# DS-1.net
KiCad netlist of a schematic drawn in Altium Designer
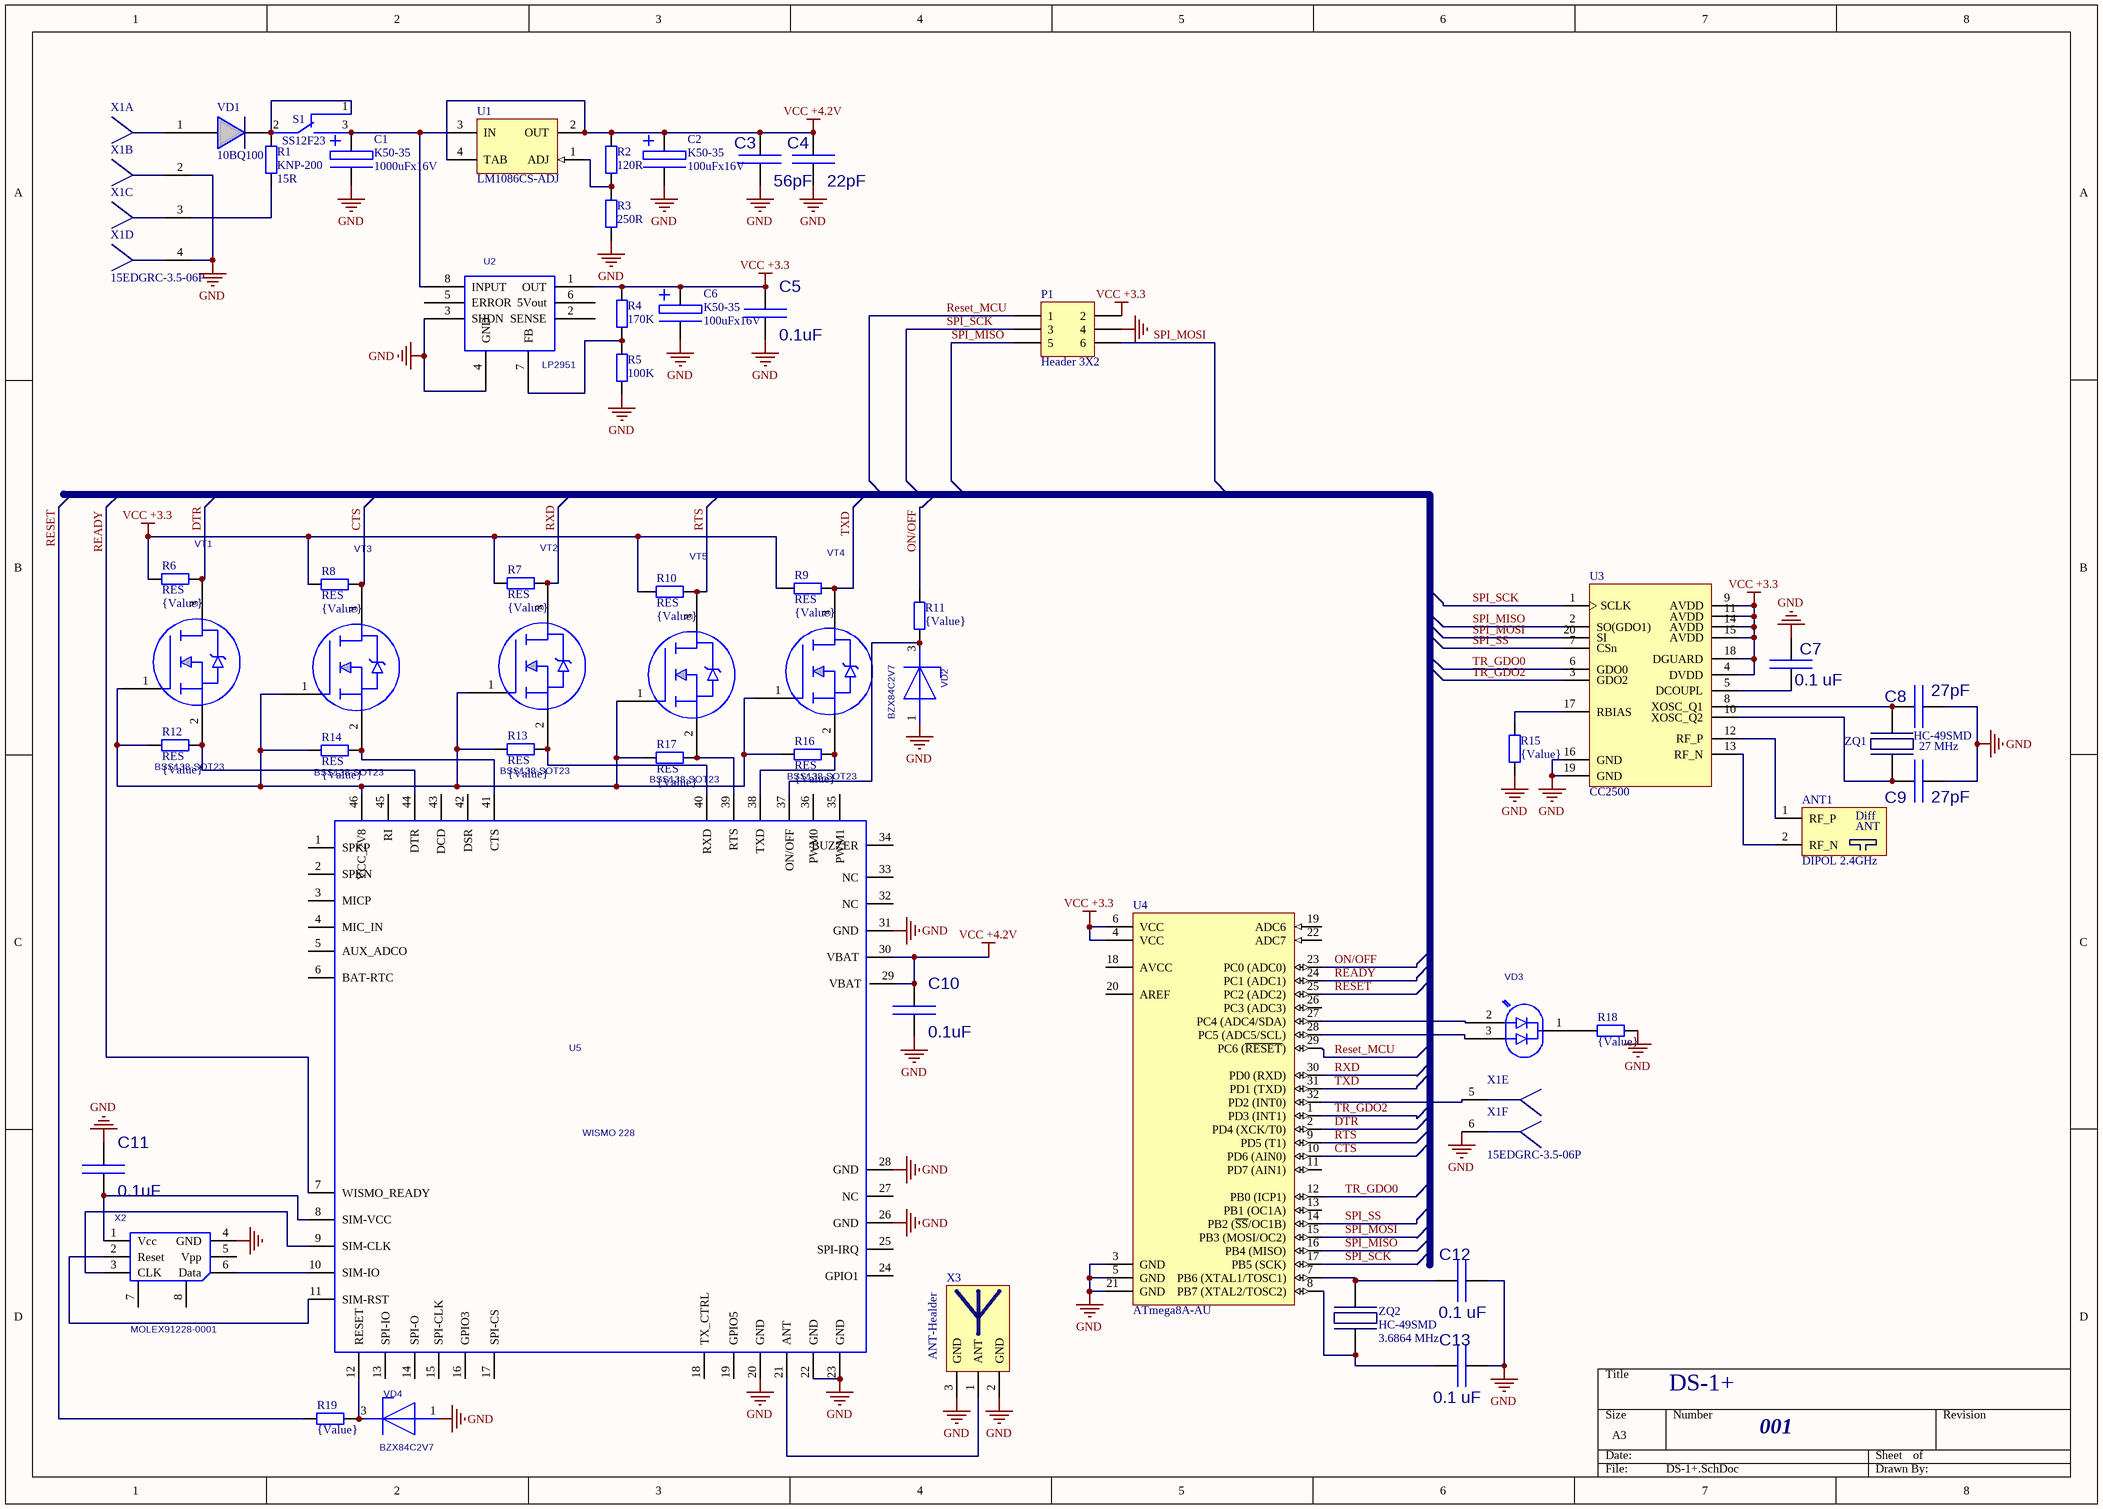
[diagram p0: DS-1+.SchDoc]

(export (version "E")
  (design (tool "Eeschema 10.0.6"))
  (components
    (comp (ref "ANT1")
      (value "DIPOL 2.4GHz")
      (footprint "ANT_Dipol_2.4GHz")
      (libsource (lib "NEW") (part "ANT_dipol_2.4GHz"))
    )
    (comp (ref "C1")
      (value "K50-35")
      (footprint "CAP_POL_D10")
      (fields (field (name "ALTIUM_VALUE") "1000uFx16V"))
      (libsource (lib "NEW") (part "Capasitor_pol D10"))
    )
    (comp (ref "C2")
      (value "K50-35")
      (footprint "CAP_POL_D6.3")
      (fields (field (name "ALTIUM_VALUE") "100uFx16V"))
      (libsource (lib "NEW") (part "Capasitor_pol D6.3"))
    )
    (comp (ref "C3")
      (value "56pF")
      (footprint "C0805")
      (description "KONDENS_SMD")
      (libsource (lib "NEW") (part "KONDENS_SMD"))
    )
    (comp (ref "C4")
      (value "22pF")
      (footprint "C0805")
      (description "KONDENS_SMD")
      (libsource (lib "NEW") (part "KONDENS_SMD"))
    )
    (comp (ref "C5")
      (value "0.1uF")
      (footprint "C0805")
      (description "KONDENS_SMD")
      (libsource (lib "NEW") (part "KONDENS_SMD"))
    )
    (comp (ref "C6")
      (value "K50-35")
      (footprint "CAP_POL_D6.3")
      (fields (field (name "ALTIUM_VALUE") "100uFx16V"))
      (libsource (lib "NEW") (part "Capasitor_pol D6.3"))
    )
    (comp (ref "C7")
      (value "0.1 uF")
      (footprint "C0805")
      (description "KONDENS_SMD")
      (libsource (lib "NEW") (part "KONDENS_SMD"))
    )
    (comp (ref "C8")
      (value "27pF")
      (footprint "C0805")
      (description "KONDENS_SMD")
      (libsource (lib "NEW") (part "KONDENS_SMD"))
    )
    (comp (ref "C9")
      (value "27pF")
      (footprint "C0805")
      (description "KONDENS_SMD")
      (libsource (lib "NEW") (part "KONDENS_SMD"))
    )
    (comp (ref "C10")
      (value "0.1uF")
      (footprint "C0805")
      (description "KONDENS_SMD")
      (libsource (lib "NEW") (part "KONDENS_SMD"))
    )
    (comp (ref "C11")
      (value "0.1uF")
      (footprint "C0805")
      (description "KONDENS_SMD")
      (libsource (lib "NEW") (part "KONDENS_SMD"))
    )
    (comp (ref "C12")
      (value "0.1 uF")
      (footprint "C0805")
      (description "KONDENS_SMD")
      (libsource (lib "NEW") (part "KONDENS_SMD"))
    )
    (comp (ref "C13")
      (value "0.1 uF")
      (footprint "C0805")
      (description "KONDENS_SMD")
      (libsource (lib "NEW") (part "KONDENS_SMD"))
    )
    (comp (ref "P1")
      (value "Header 3X2")
      (footprint "HDR2X3")
      (description "Header, 3-Pin, Dual row")
      (fields (field (name "PUBLISHER") "Altium Limited"))
      (libsource (lib "Miscellaneous Connectors") (part "Header 3X2"))
    )
    (comp (ref "R1")
      (value "KNP-200")
      (footprint "Resistor KNP-200")
      (fields (field (name "ALTIUM_VALUE") "15R"))
      (libsource (lib "NEW") (part "Resistor 2W"))
    )
    (comp (ref "R2")
      (value "120R")
      (footprint "C0805")
      (description "Resistor")
      (fields (field (name "Comment") "RES"))
      (libsource (lib "") (part "RES_1"))
    )
    (comp (ref "R3")
      (value "250R")
      (footprint "C0805")
      (description "Resistor")
      (fields (field (name "Comment") "RES"))
      (libsource (lib "") (part "RES_1"))
    )
    (comp (ref "R4")
      (value "170K")
      (footprint "C0805")
      (description "Resistor")
      (fields (field (name "Comment") "RES"))
      (libsource (lib "") (part "RES_1"))
    )
    (comp (ref "R5")
      (value "100K")
      (footprint "C0805")
      (description "Resistor")
      (fields (field (name "Comment") "RES"))
      (libsource (lib "") (part "RES_1"))
    )
    (comp (ref "R6")
      (value "RES")
      (footprint "C0805")
      (description "Resistor")
      (fields (field (name "ALTIUM_VALUE") "{Value}"))
      (libsource (lib "NEW") (part "RES"))
    )
    (comp (ref "R7")
      (value "RES")
      (footprint "C0805")
      (description "Resistor")
      (fields (field (name "ALTIUM_VALUE") "{Value}"))
      (libsource (lib "NEW") (part "RES"))
    )
    (comp (ref "R8")
      (value "RES")
      (footprint "C0805")
      (description "Resistor")
      (fields (field (name "ALTIUM_VALUE") "{Value}"))
      (libsource (lib "NEW") (part "RES"))
    )
    (comp (ref "R9")
      (value "RES")
      (footprint "C0805")
      (description "Resistor")
      (fields (field (name "ALTIUM_VALUE") "{Value}"))
      (libsource (lib "NEW") (part "RES"))
    )
    (comp (ref "R10")
      (value "RES")
      (footprint "C0805")
      (description "Resistor")
      (fields (field (name "ALTIUM_VALUE") "{Value}"))
      (libsource (lib "NEW") (part "RES"))
    )
    (comp (ref "R11")
      (value "{Value}")
      (footprint "C0805")
      (description "Resistor")
      (fields (field (name "Comment") "RES"))
      (libsource (lib "") (part "RES_1"))
    )
    (comp (ref "R12")
      (value "RES")
      (footprint "C0805")
      (description "Resistor")
      (fields (field (name "ALTIUM_VALUE") "{Value}"))
      (libsource (lib "NEW") (part "RES"))
    )
    (comp (ref "R13")
      (value "RES")
      (footprint "C0805")
      (description "Resistor")
      (fields (field (name "ALTIUM_VALUE") "{Value}"))
      (libsource (lib "NEW") (part "RES"))
    )
    (comp (ref "R14")
      (value "RES")
      (footprint "C0805")
      (description "Resistor")
      (fields (field (name "ALTIUM_VALUE") "{Value}"))
      (libsource (lib "NEW") (part "RES"))
    )
    (comp (ref "R15")
      (value "{Value}")
      (footprint "C0805")
      (description "Resistor")
      (fields (field (name "Comment") "RES"))
      (libsource (lib "") (part "RES_1"))
    )
    (comp (ref "R16")
      (value "RES")
      (footprint "C0805")
      (description "Resistor")
      (fields (field (name "ALTIUM_VALUE") "{Value}"))
      (libsource (lib "NEW") (part "RES"))
    )
    (comp (ref "R17")
      (value "RES")
      (footprint "C0805")
      (description "Resistor")
      (fields (field (name "ALTIUM_VALUE") "{Value}"))
      (libsource (lib "NEW") (part "RES"))
    )
    (comp (ref "R18")
      (value "{Value}")
      (footprint "C0805")
      (description "Resistor")
      (fields (field (name "Comment") "RES"))
      (libsource (lib "NEW") (part "RES"))
    )
    (comp (ref "R19")
      (value "{Value}")
      (footprint "C0805")
      (description "Resistor")
      (fields (field (name "Comment") "RES"))
      (libsource (lib "NEW") (part "RES"))
    )
    (comp (ref "S1") (value "SS12F23") (footprint "SS12F23") (libsource (lib "NEW") (part "SS12F23")))
    (comp (ref "U1")
      (value "LM1086CS-ADJ")
      (footprint "TS3B_M")
      (description "1.5A Low Dropout Positive Regulators, 3-pin TO-263")
      (fields
        (field (name "MANUFACTURER") "National Semiconductor")
        (field (name "PUBLISHER") "Altium Limited")
      )
      (libsource (lib "NSC LDO") (part "LM1086CS-ADJ"))
    )
    (comp (ref "U2") (value "LP2951") (footprint "SOIC-8") (libsource (lib "NEW") (part "LP2951")))
    (comp (ref "U3") (value "CC2500") (footprint "VQFN20") (libsource (lib "NEW") (part "CC2500")))
    (comp (ref "U4")
      (value "ATmega8A-AU")
      (footprint "32A_M")
      (fields (field (name "PUBLISHER") "Altium Limited"))
      (libsource (lib "Atmel Microcontroller 8-Bit megaAVR") (part "ATmega8A-AU"))
    )
    (comp (ref "U5") (value "WISMO 228") (footprint "WISMO") (libsource (lib "NEW") (part "WISMO 228")))
    (comp (ref "VD1") (value "10BQ100") (footprint "SMB") (libsource (lib "NEW") (part "10BQ100")))
    (comp (ref "VD2") (value "BZX84C2V7") (footprint "SOT23") (libsource (lib "NEW") (part "BZX84C2V7")))
    (comp (ref "VD3")
      (value "LIGHTDIODE2")
      (footprint "LIGHTDIODE2")
      (libsource (lib "NEW") (part "LIGHTDIODE2"))
    )
    (comp (ref "VD4") (value "BZX84C2V7") (footprint "SOT23") (libsource (lib "NEW") (part "BZX84C2V7")))
    (comp (ref "VT1")
      (value "BSS138-SOT23")
      (footprint "SOT23")
      (libsource (lib "NEW") (part "BSS138-SOT23"))
    )
    (comp (ref "VT2")
      (value "BSS138-SOT23")
      (footprint "SOT23")
      (libsource (lib "NEW") (part "BSS138-SOT23"))
    )
    (comp (ref "VT3")
      (value "BSS138-SOT23")
      (footprint "SOT23")
      (libsource (lib "NEW") (part "BSS138-SOT23"))
    )
    (comp (ref "VT4")
      (value "BSS138-SOT23")
      (footprint "SOT23")
      (libsource (lib "NEW") (part "BSS138-SOT23"))
    )
    (comp (ref "VT5")
      (value "BSS138-SOT23")
      (footprint "SOT23")
      (libsource (lib "NEW") (part "BSS138-SOT23"))
    )
    (comp (ref "X1")
      (value "15EDGRC-3.5-06P")
      (footprint "15EDGRC-3.5-06P")
      (libsource (lib "NEW") (part "15EDGRC-3.5-06P"))
    )
    (comp (ref "X2")
      (value "MOLEX91228-0001")
      (footprint "MOLEX91228-0001")
      (libsource (lib "NEW") (part "MOLEX91228-0001"))
    )
    (comp (ref "X3")
      (value "ANT-Healder")
      (footprint "ANT-Healder")
      (libsource (lib "NEW") (part "ANT_HELDER"))
    )
    (comp (ref "ZQ1")
      (value "HC-49SMD")
      (footprint "HC-49SMD")
      (fields (field (name "ALTIUM_VALUE") "27 MHz"))
      (libsource (lib "NEW") (part "HC-49SMD"))
    )
    (comp (ref "ZQ2")
      (value "HC-49SMD")
      (footprint "HC-49SMD")
      (fields (field (name "ALTIUM_VALUE") "3.6864 MHz"))
      (libsource (lib "NEW") (part "HC-49SMD"))
    )
  )
  (nets
    (net (code "1") (name "/CTS") (class "Default")
      (node (ref "R8") (pin "2") (pinfunction "2_2") (pintype "passive"))
      (node (ref "U4") (pin "10") (pinfunction "PD6_(AIN0)_10") (pintype "bidirectional"))
      (node (ref "VT3") (pin "3") (pinfunction "Drain_3") (pintype "passive"))
    )
    (net (code "2") (name "/DTR") (class "Default")
      (node (ref "R6") (pin "2") (pinfunction "2_2") (pintype "passive"))
      (node (ref "U4") (pin "2") (pinfunction "PD4_(XCK/T0)_2") (pintype "bidirectional"))
      (node (ref "VT1") (pin "3") (pinfunction "Drain_3") (pintype "passive"))
    )
    (net (code "3") (name "/ON{slash}OFF") (class "Default")
      (node (ref "R11") (pin "2") (pinfunction "2_2") (pintype "passive"))
      (node (ref "U4") (pin "23") (pinfunction "PC0_(ADC0)_23") (pintype "bidirectional"))
    )
    (net (code "4") (name "/READY") (class "Default")
      (node (ref "U4") (pin "24") (pinfunction "PC1_(ADC1)_24") (pintype "bidirectional"))
      (node (ref "U5") (pin "7") (pinfunction "WISMO_READY_7") (pintype "passive"))
    )
    (net (code "5") (name "/RESET") (class "Default")
      (node (ref "R19") (pin "1") (pinfunction "1_1") (pintype "passive"))
      (node (ref "U4") (pin "25") (pinfunction "PC2_(ADC2)_25") (pintype "bidirectional"))
    )
    (net (code "6") (name "/RTS") (class "Default")
      (node (ref "R10") (pin "2") (pinfunction "2_2") (pintype "passive"))
      (node (ref "U4") (pin "9") (pinfunction "PD5_(T1)_9") (pintype "bidirectional"))
      (node (ref "VT5") (pin "3") (pinfunction "Drain_3") (pintype "passive"))
    )
    (net (code "7") (name "/RXD") (class "Default")
      (node (ref "R7") (pin "2") (pinfunction "2_2") (pintype "passive"))
      (node (ref "U4") (pin "30") (pinfunction "PD0_(RXD)_30") (pintype "bidirectional"))
      (node (ref "VT2") (pin "3") (pinfunction "Drain_3") (pintype "passive"))
    )
    (net (code "8") (name "/Reset_MCU") (class "Default")
      (node (ref "P1") (pin "1") (pinfunction "1_1") (pintype "passive"))
      (node (ref "U4") (pin "29") (pinfunction "PC6_(~{RESET})_29") (pintype "bidirectional"))
    )
    (net (code "9") (name "/SPI_MISO") (class "Default")
      (node (ref "P1") (pin "5") (pinfunction "5_5") (pintype "passive"))
      (node (ref "U3") (pin "2") (pinfunction "SO(GDO1)_2") (pintype "passive"))
      (node (ref "U4") (pin "16") (pinfunction "PB4_(MISO)_16") (pintype "bidirectional"))
    )
    (net (code "10") (name "/SPI_MOSI") (class "Default")
      (node (ref "P1") (pin "6") (pinfunction "6_6") (pintype "passive"))
      (node (ref "U3") (pin "20") (pinfunction "SI_20") (pintype "passive"))
      (node (ref "U4") (pin "15") (pinfunction "PB3_(MOSI/OC2)_15") (pintype "bidirectional"))
    )
    (net (code "11") (name "/SPI_SCK") (class "Default")
      (node (ref "P1") (pin "3") (pinfunction "3_3") (pintype "passive"))
      (node (ref "U3") (pin "1") (pinfunction "SCLK_1") (pintype "passive"))
      (node (ref "U4") (pin "17") (pinfunction "PB5_(SCK)_17") (pintype "bidirectional"))
    )
    (net (code "12") (name "/SPI_SS") (class "Default")
      (node (ref "U3") (pin "7") (pinfunction "CSn_7") (pintype "passive"))
      (node (ref "U4") (pin "14") (pinfunction "PB2_(~{SS}/OC1B)_14") (pintype "bidirectional"))
    )
    (net (code "13") (name "/TR_GDO0") (class "Default")
      (node (ref "U3") (pin "6") (pinfunction "GDO0_6") (pintype "passive"))
      (node (ref "U4") (pin "12") (pinfunction "PB0_(ICP1)_12") (pintype "bidirectional"))
    )
    (net (code "14") (name "/TR_GDO2") (class "Default")
      (node (ref "U3") (pin "3") (pinfunction "GDO2_3") (pintype "passive"))
      (node (ref "U4") (pin "1") (pinfunction "PD3_(INT1)_1") (pintype "bidirectional"))
    )
    (net (code "15") (name "/TXD") (class "Default")
      (node (ref "R9") (pin "2") (pinfunction "2_2") (pintype "passive"))
      (node (ref "U4") (pin "31") (pinfunction "PD1_(TXD)_31") (pintype "bidirectional"))
      (node (ref "VT4") (pin "3") (pinfunction "Drain_3") (pintype "passive"))
    )
    (net (code "16") (name "GND") (class "Default")
      (node (ref "C1") (pin "2") (pinfunction "MINUS_2") (pintype "passive"))
      (node (ref "C10") (pin "2") (pinfunction "B_2") (pintype "passive"))
      (node (ref "C11") (pin "1") (pinfunction "A_1") (pintype "passive"))
      (node (ref "C12") (pin "2") (pinfunction "B_2") (pintype "passive"))
      (node (ref "C13") (pin "2") (pinfunction "B_2") (pintype "passive"))
      (node (ref "C2") (pin "2") (pinfunction "MINUS_2") (pintype "passive"))
      (node (ref "C3") (pin "2") (pinfunction "B_2") (pintype "passive"))
      (node (ref "C4") (pin "2") (pinfunction "B_2") (pintype "passive"))
      (node (ref "C5") (pin "2") (pinfunction "B_2") (pintype "passive"))
      (node (ref "C6") (pin "2") (pinfunction "MINUS_2") (pintype "passive"))
      (node (ref "C7") (pin "2") (pinfunction "B_2") (pintype "passive"))
      (node (ref "C8") (pin "2") (pinfunction "B_2") (pintype "passive"))
      (node (ref "C9") (pin "2") (pinfunction "B_2") (pintype "passive"))
      (node (ref "P1") (pin "4") (pinfunction "4_4") (pintype "passive"))
      (node (ref "R15") (pin "1") (pinfunction "1_1") (pintype "passive"))
      (node (ref "R18") (pin "2") (pinfunction "2_2") (pintype "passive"))
      (node (ref "R3") (pin "1") (pinfunction "1_1") (pintype "passive"))
      (node (ref "R5") (pin "1") (pinfunction "1_1") (pintype "passive"))
      (node (ref "U2") (pin "3") (pinfunction "SHDN_3") (pintype "passive"))
      (node (ref "U2") (pin "4") (pinfunction "GND_4") (pintype "passive"))
      (node (ref "U3") (pin "16") (pinfunction "GND_16") (pintype "passive"))
      (node (ref "U3") (pin "19") (pinfunction "GND_19") (pintype "passive"))
      (node (ref "U4") (pin "21") (pinfunction "GND_21") (pintype "power_in"))
      (node (ref "U4") (pin "3") (pinfunction "GND_3") (pintype "power_in"))
      (node (ref "U4") (pin "5") (pinfunction "GND_5") (pintype "power_in"))
      (node (ref "U5") (pin "20") (pinfunction "GND_20") (pintype "passive"))
      (node (ref "U5") (pin "22") (pinfunction "GND_22") (pintype "passive"))
      (node (ref "U5") (pin "23") (pinfunction "GND_23") (pintype "passive"))
      (node (ref "U5") (pin "26") (pinfunction "GND_26") (pintype "passive"))
      (node (ref "U5") (pin "28") (pinfunction "GND_28") (pintype "passive"))
      (node (ref "U5") (pin "31") (pinfunction "GND_31") (pintype "passive"))
      (node (ref "VD2") (pin "1") (pinfunction "1_1") (pintype "passive"))
      (node (ref "VD4") (pin "1") (pinfunction "1_1") (pintype "passive"))
      (node (ref "X1") (pin "2") (pinfunction "2_2") (pintype "passive"))
      (node (ref "X1") (pin "4") (pinfunction "4_4") (pintype "passive"))
      (node (ref "X1") (pin "6") (pinfunction "6_6") (pintype "passive"))
      (node (ref "X2") (pin "4") (pinfunction "GND_4") (pintype "passive"))
      (node (ref "X3") (pin "2") (pinfunction "GND_2") (pintype "passive"))
      (node (ref "X3") (pin "3") (pinfunction "GND_3") (pintype "passive"))
    )
    (net (code "17") (name "Net-(ANT1-RF_N)") (class "Default")
      (node (ref "ANT1") (pin "2") (pinfunction "RF_N_2") (pintype "passive"))
      (node (ref "U3") (pin "13") (pinfunction "RF_N_13") (pintype "passive"))
    )
    (net (code "18") (name "Net-(ANT1-RF_P)") (class "Default")
      (node (ref "ANT1") (pin "1") (pinfunction "RF_P_1") (pintype "passive"))
      (node (ref "U3") (pin "12") (pinfunction "RF_P_12") (pintype "passive"))
    )
    (net (code "19") (name "Net-(C1-PLUS)") (class "Default")
      (node (ref "C1") (pin "1") (pinfunction "PLUS_1") (pintype "passive"))
      (node (ref "S1") (pin "3") (pinfunction "3_3") (pintype "passive"))
      (node (ref "U1") (pin "3") (pinfunction "IN_3") (pintype "power_in"))
      (node (ref "U2") (pin "8") (pinfunction "INPUT_8") (pintype "passive"))
    )
    (net (code "20") (name "Net-(C7-A)") (class "Default")
      (node (ref "C7") (pin "1") (pinfunction "A_1") (pintype "passive"))
      (node (ref "U3") (pin "5") (pinfunction "DCOUPL_5") (pintype "passive"))
    )
    (net (code "21") (name "Net-(C8-A)") (class "Default")
      (node (ref "C8") (pin "1") (pinfunction "A_1") (pintype "passive"))
      (node (ref "U3") (pin "8") (pinfunction "XOSC_Q1_8") (pintype "passive"))
      (node (ref "ZQ1") (pin "1") (pinfunction "1_1") (pintype "passive"))
    )
    (net (code "22") (name "Net-(C9-A)") (class "Default")
      (node (ref "C9") (pin "1") (pinfunction "A_1") (pintype "passive"))
      (node (ref "U3") (pin "10") (pinfunction "XOSC_Q2_10") (pintype "passive"))
      (node (ref "ZQ1") (pin "2") (pinfunction "2_2") (pintype "passive"))
    )
    (net (code "23") (name "Net-(C11-B)") (class "Default")
      (node (ref "C11") (pin "2") (pinfunction "B_2") (pintype "passive"))
      (node (ref "U5") (pin "8") (pinfunction "SIM-VCC_8") (pintype "passive"))
      (node (ref "X2") (pin "1") (pinfunction "Vcc_1") (pintype "passive"))
    )
    (net (code "24") (name "Net-(C12-A)") (class "Default")
      (node (ref "C12") (pin "1") (pinfunction "A_1") (pintype "passive"))
      (node (ref "U4") (pin "7") (pinfunction "PB6_(XTAL1/TOSC1)_7") (pintype "bidirectional"))
      (node (ref "ZQ2") (pin "1") (pinfunction "1_1") (pintype "passive"))
    )
    (net (code "25") (name "Net-(C13-A)") (class "Default")
      (node (ref "C13") (pin "1") (pinfunction "A_1") (pintype "passive"))
      (node (ref "U4") (pin "8") (pinfunction "PB7_(XTAL2/TOSC2)_8") (pintype "bidirectional"))
      (node (ref "ZQ2") (pin "2") (pinfunction "2_2") (pintype "passive"))
    )
    (net (code "26") (name "Net-(R1-Pad1)") (class "Default")
      (node (ref "R1") (pin "1") (pinfunction "1_1") (pintype "passive"))
      (node (ref "X1") (pin "3") (pinfunction "3_3") (pintype "passive"))
    )
    (net (code "27") (name "Net-(R1-Pad2)") (class "Default")
      (node (ref "R1") (pin "2") (pinfunction "2_2") (pintype "passive"))
      (node (ref "S1") (pin "1") (pinfunction "1_1") (pintype "passive"))
      (node (ref "S1") (pin "2") (pinfunction "2_2") (pintype "passive"))
      (node (ref "VD1") (pin "1") (pinfunction "1_1") (pintype "passive"))
    )
    (net (code "28") (name "Net-(R18-Pad1)") (class "Default")
      (node (ref "R18") (pin "1") (pinfunction "1_1") (pintype "passive"))
      (node (ref "VD3") (pin "1") (pintype "passive"))
    )
    (net (code "29") (name "Net-(U1-ADJ)") (class "Default")
      (node (ref "R2") (pin "1") (pinfunction "1_1") (pintype "passive"))
      (node (ref "R3") (pin "2") (pinfunction "2_2") (pintype "passive"))
      (node (ref "U1") (pin "1") (pinfunction "ADJ_1") (pintype "input"))
    )
    (net (code "30") (name "Net-(U2-FB)") (class "Default")
      (node (ref "R4") (pin "1") (pinfunction "1_1") (pintype "passive"))
      (node (ref "R5") (pin "2") (pinfunction "2_2") (pintype "passive"))
      (node (ref "U2") (pin "7") (pinfunction "FB_7") (pintype "passive"))
    )
    (net (code "31") (name "Net-(U3-RBIAS)") (class "Default")
      (node (ref "R15") (pin "2") (pinfunction "2_2") (pintype "passive"))
      (node (ref "U3") (pin "17") (pinfunction "RBIAS_17") (pintype "passive"))
    )
    (net (code "32") (name "Net-(U4-PC4_(ADC4{slash}SDA))") (class "Default")
      (node (ref "U4") (pin "27") (pinfunction "PC4_(ADC4/SDA)_27") (pintype "bidirectional"))
      (node (ref "VD3") (pin "2") (pintype "passive"))
    )
    (net (code "33") (name "Net-(U4-PC5_(ADC5{slash}SCL))") (class "Default")
      (node (ref "U4") (pin "28") (pinfunction "PC5_(ADC5/SCL)_28") (pintype "bidirectional"))
      (node (ref "VD3") (pin "3") (pintype "passive"))
    )
    (net (code "34") (name "Net-(U4-PD2_(INT0))") (class "Default")
      (node (ref "U4") (pin "32") (pinfunction "PD2_(INT0)_32") (pintype "bidirectional"))
      (node (ref "X1") (pin "5") (pinfunction "5_5") (pintype "passive"))
    )
    (net (code "35") (name "Net-(U5-ANT)") (class "Default")
      (node (ref "U5") (pin "21") (pinfunction "ANT_21") (pintype "passive"))
      (node (ref "X3") (pin "1") (pinfunction "ANT_1") (pintype "passive"))
    )
    (net (code "36") (name "Net-(U5-CTS)") (class "Default")
      (node (ref "R14") (pin "2") (pinfunction "2_2") (pintype "passive"))
      (node (ref "U5") (pin "41") (pinfunction "CTS_41") (pintype "passive"))
      (node (ref "VT3") (pin "2") (pinfunction "Source_2") (pintype "passive"))
    )
    (net (code "37") (name "Net-(U5-DTR)") (class "Default")
      (node (ref "R12") (pin "2") (pinfunction "2_2") (pintype "passive"))
      (node (ref "U5") (pin "44") (pinfunction "DTR_44") (pintype "passive"))
      (node (ref "VT1") (pin "2") (pinfunction "Source_2") (pintype "passive"))
    )
    (net (code "38") (name "Net-(U5-ON{slash}OFF)") (class "Default")
      (node (ref "R11") (pin "1") (pinfunction "1_1") (pintype "passive"))
      (node (ref "U5") (pin "37") (pinfunction "ON/OFF_37") (pintype "passive"))
      (node (ref "VD2") (pin "3") (pinfunction "2_3") (pintype "passive"))
    )
    (net (code "39") (name "Net-(U5-RESET)") (class "Default")
      (node (ref "R19") (pin "2") (pinfunction "2_2") (pintype "passive"))
      (node (ref "U5") (pin "12") (pinfunction "RESET_12") (pintype "passive"))
      (node (ref "VD4") (pin "3") (pinfunction "2_3") (pintype "passive"))
    )
    (net (code "40") (name "Net-(U5-RTS)") (class "Default")
      (node (ref "R17") (pin "2") (pinfunction "2_2") (pintype "passive"))
      (node (ref "U5") (pin "39") (pinfunction "RTS_39") (pintype "passive"))
      (node (ref "VT5") (pin "2") (pinfunction "Source_2") (pintype "passive"))
    )
    (net (code "41") (name "Net-(U5-RXD)") (class "Default")
      (node (ref "R13") (pin "2") (pinfunction "2_2") (pintype "passive"))
      (node (ref "U5") (pin "40") (pinfunction "RXD_40") (pintype "passive"))
      (node (ref "VT2") (pin "2") (pinfunction "Source_2") (pintype "passive"))
    )
    (net (code "42") (name "Net-(U5-SIM-CLK)") (class "Default")
      (node (ref "U5") (pin "9") (pinfunction "SIM-CLK_9") (pintype "passive"))
      (node (ref "X2") (pin "3") (pinfunction "CLK_3") (pintype "passive"))
    )
    (net (code "43") (name "Net-(U5-SIM-IO)") (class "Default")
      (node (ref "U5") (pin "10") (pinfunction "SIM-IO_10") (pintype "passive"))
      (node (ref "X2") (pin "6") (pinfunction "Data_6") (pintype "passive"))
    )
    (net (code "44") (name "Net-(U5-SIM-RST)") (class "Default")
      (node (ref "U5") (pin "11") (pinfunction "SIM-RST_11") (pintype "passive"))
      (node (ref "X2") (pin "2") (pinfunction "Reset_2") (pintype "passive"))
    )
    (net (code "45") (name "Net-(U5-TXD)") (class "Default")
      (node (ref "R16") (pin "2") (pinfunction "2_2") (pintype "passive"))
      (node (ref "U5") (pin "38") (pinfunction "TXD_38") (pintype "passive"))
      (node (ref "VT4") (pin "2") (pinfunction "Source_2") (pintype "passive"))
    )
    (net (code "46") (name "Net-(U5-VCC_2V8)") (class "Default")
      (node (ref "R12") (pin "1") (pinfunction "1_1") (pintype "passive"))
      (node (ref "R13") (pin "1") (pinfunction "1_1") (pintype "passive"))
      (node (ref "R14") (pin "1") (pinfunction "1_1") (pintype "passive"))
      (node (ref "R16") (pin "1") (pinfunction "1_1") (pintype "passive"))
      (node (ref "R17") (pin "1") (pinfunction "1_1") (pintype "passive"))
      (node (ref "U5") (pin "46") (pinfunction "VCC_2V8_46") (pintype "passive"))
      (node (ref "VT1") (pin "1") (pinfunction "Gate_1") (pintype "passive"))
      (node (ref "VT2") (pin "1") (pinfunction "Gate_1") (pintype "passive"))
      (node (ref "VT3") (pin "1") (pinfunction "Gate_1") (pintype "passive"))
      (node (ref "VT4") (pin "1") (pinfunction "Gate_1") (pintype "passive"))
      (node (ref "VT5") (pin "1") (pinfunction "Gate_1") (pintype "passive"))
    )
    (net (code "47") (name "Net-(VD1-Pad2)") (class "Default")
      (node (ref "VD1") (pin "2") (pinfunction "2_2") (pintype "passive"))
      (node (ref "X1") (pin "1") (pinfunction "1_1") (pintype "passive"))
    )
    (net (code "48") (name "VCC +3.3") (class "Default")
      (node (ref "C5") (pin "1") (pinfunction "A_1") (pintype "passive"))
      (node (ref "C6") (pin "1") (pinfunction "PLUS_1") (pintype "passive"))
      (node (ref "P1") (pin "2") (pinfunction "2_2") (pintype "passive"))
      (node (ref "R10") (pin "1") (pinfunction "1_1") (pintype "passive"))
      (node (ref "R4") (pin "2") (pinfunction "2_2") (pintype "passive"))
      (node (ref "R6") (pin "1") (pinfunction "1_1") (pintype "passive"))
      (node (ref "R7") (pin "1") (pinfunction "1_1") (pintype "passive"))
      (node (ref "R8") (pin "1") (pinfunction "1_1") (pintype "passive"))
      (node (ref "R9") (pin "1") (pinfunction "1_1") (pintype "passive"))
      (node (ref "U2") (pin "1") (pinfunction "OUT_1") (pintype "passive"))
      (node (ref "U3") (pin "11") (pinfunction "AVDD_11") (pintype "passive"))
      (node (ref "U3") (pin "14") (pinfunction "AVDD_14") (pintype "passive"))
      (node (ref "U3") (pin "15") (pinfunction "AVDD_15") (pintype "passive"))
      (node (ref "U3") (pin "18") (pinfunction "DGUARD_18") (pintype "passive"))
      (node (ref "U3") (pin "4") (pinfunction "DVDD_4") (pintype "passive"))
      (node (ref "U3") (pin "9") (pinfunction "AVDD_9") (pintype "passive"))
      (node (ref "U4") (pin "4") (pinfunction "VCC_4") (pintype "power_in"))
      (node (ref "U4") (pin "6") (pinfunction "VCC_6") (pintype "power_in"))
    )
    (net (code "49") (name "VCC +4.2V") (class "Default")
      (node (ref "C10") (pin "1") (pinfunction "A_1") (pintype "passive"))
      (node (ref "C2") (pin "1") (pinfunction "PLUS_1") (pintype "passive"))
      (node (ref "C3") (pin "1") (pinfunction "A_1") (pintype "passive"))
      (node (ref "C4") (pin "1") (pinfunction "A_1") (pintype "passive"))
      (node (ref "R2") (pin "2") (pinfunction "2_2") (pintype "passive"))
      (node (ref "U1") (pin "2") (pinfunction "OUT_2") (pintype "power_in"))
      (node (ref "U1") (pin "4") (pinfunction "TAB_4") (pintype "power_in"))
      (node (ref "U5") (pin "29") (pinfunction "VBAT_29") (pintype "passive"))
      (node (ref "U5") (pin "30") (pinfunction "VBAT_30") (pintype "passive"))
    )
    (net (code "50") (name "unconnected-(U2-5Vout-Pad6)") (class "Default")
      (node (ref "U2") (pin "6") (pinfunction "5Vout_6") (pintype "passive"))
    )
    (net (code "51") (name "unconnected-(U2-ERROR-Pad5)") (class "Default")
      (node (ref "U2") (pin "5") (pinfunction "ERROR_5") (pintype "passive"))
    )
    (net (code "52") (name "unconnected-(U2-SENSE-Pad2)") (class "Default")
      (node (ref "U2") (pin "2") (pinfunction "SENSE_2") (pintype "passive"))
    )
    (net (code "53") (name "unconnected-(U4-ADC6-Pad19)") (class "Default")
      (node (ref "U4") (pin "19") (pinfunction "ADC6_19") (pintype "input"))
    )
    (net (code "54") (name "unconnected-(U4-ADC7-Pad22)") (class "Default")
      (node (ref "U4") (pin "22") (pinfunction "ADC7_22") (pintype "input"))
    )
    (net (code "55") (name "unconnected-(U4-AREF-Pad20)") (class "Default")
      (node (ref "U4") (pin "20") (pinfunction "AREF_20") (pintype "power_in"))
    )
    (net (code "56") (name "unconnected-(U4-AVCC-Pad18)") (class "Default")
      (node (ref "U4") (pin "18") (pinfunction "AVCC_18") (pintype "power_in"))
    )
    (net (code "57") (name "unconnected-(U4-PB1_(OC1A)-Pad13)") (class "Default")
      (node (ref "U4") (pin "13") (pinfunction "PB1_(OC1A)_13") (pintype "bidirectional"))
    )
    (net (code "58") (name "unconnected-(U4-PC3_(ADC3)-Pad26)") (class "Default")
      (node (ref "U4") (pin "26") (pinfunction "PC3_(ADC3)_26") (pintype "bidirectional"))
    )
    (net (code "59") (name "unconnected-(U4-PD7_(AIN1)-Pad11)") (class "Default")
      (node (ref "U4") (pin "11") (pinfunction "PD7_(AIN1)_11") (pintype "bidirectional"))
    )
    (net (code "60") (name "unconnected-(U5-AUX_ADCO-Pad5)") (class "Default")
      (node (ref "U5") (pin "5") (pinfunction "AUX_ADCO_5") (pintype "passive"))
    )
    (net (code "61") (name "unconnected-(U5-BAT-RTC-Pad6)") (class "Default")
      (node (ref "U5") (pin "6") (pinfunction "BAT-RTC_6") (pintype "passive"))
    )
    (net (code "62") (name "unconnected-(U5-BUZZER-Pad34)") (class "Default")
      (node (ref "U5") (pin "34") (pinfunction "BUZZER_34") (pintype "passive"))
    )
    (net (code "63") (name "unconnected-(U5-DCD-Pad43)") (class "Default")
      (node (ref "U5") (pin "43") (pinfunction "DCD_43") (pintype "passive"))
    )
    (net (code "64") (name "unconnected-(U5-DSR-Pad42)") (class "Default")
      (node (ref "U5") (pin "42") (pinfunction "DSR_42") (pintype "passive"))
    )
    (net (code "65") (name "unconnected-(U5-GPIO1-Pad24)") (class "Default")
      (node (ref "U5") (pin "24") (pinfunction "GPIO1_24") (pintype "passive"))
    )
    (net (code "66") (name "unconnected-(U5-GPIO3-Pad16)") (class "Default")
      (node (ref "U5") (pin "16") (pinfunction "GPIO3_16") (pintype "passive"))
    )
    (net (code "67") (name "unconnected-(U5-GPIO5-Pad19)") (class "Default")
      (node (ref "U5") (pin "19") (pinfunction "GPIO5_19") (pintype "passive"))
    )
    (net (code "68") (name "unconnected-(U5-MICP-Pad3)") (class "Default")
      (node (ref "U5") (pin "3") (pinfunction "MICP_3") (pintype "passive"))
    )
    (net (code "69") (name "unconnected-(U5-MIC_IN-Pad4)") (class "Default")
      (node (ref "U5") (pin "4") (pinfunction "MIC_IN_4") (pintype "passive"))
    )
    (net (code "70") (name "unconnected-(U5-NC-Pad27)") (class "Default")
      (node (ref "U5") (pin "27") (pinfunction "NC_27") (pintype "passive"))
    )
    (net (code "71") (name "unconnected-(U5-NC-Pad32)") (class "Default")
      (node (ref "U5") (pin "32") (pinfunction "NC_32") (pintype "passive"))
    )
    (net (code "72") (name "unconnected-(U5-NC-Pad33)") (class "Default")
      (node (ref "U5") (pin "33") (pinfunction "NC_33") (pintype "passive"))
    )
    (net (code "73") (name "unconnected-(U5-PWM0-Pad36)") (class "Default")
      (node (ref "U5") (pin "36") (pinfunction "PWM0_36") (pintype "passive"))
    )
    (net (code "74") (name "unconnected-(U5-PWM1-Pad35)") (class "Default")
      (node (ref "U5") (pin "35") (pinfunction "PWM1_35") (pintype "passive"))
    )
    (net (code "75") (name "unconnected-(U5-RI-Pad45)") (class "Default")
      (node (ref "U5") (pin "45") (pinfunction "RI_45") (pintype "passive"))
    )
    (net (code "76") (name "unconnected-(U5-SPI-CLK-Pad15)") (class "Default")
      (node (ref "U5") (pin "15") (pinfunction "SPI-CLK_15") (pintype "passive"))
    )
    (net (code "77") (name "unconnected-(U5-SPI-CS-Pad17)") (class "Default")
      (node (ref "U5") (pin "17") (pinfunction "SPI-CS_17") (pintype "passive"))
    )
    (net (code "78") (name "unconnected-(U5-SPI-IO-Pad13)") (class "Default")
      (node (ref "U5") (pin "13") (pinfunction "SPI-IO_13") (pintype "passive"))
    )
    (net (code "79") (name "unconnected-(U5-SPI-IRQ-Pad25)") (class "Default")
      (node (ref "U5") (pin "25") (pinfunction "SPI-IRQ_25") (pintype "passive"))
    )
    (net (code "80") (name "unconnected-(U5-SPI-O-Pad14)") (class "Default")
      (node (ref "U5") (pin "14") (pinfunction "SPI-O_14") (pintype "passive"))
    )
    (net (code "81") (name "unconnected-(U5-SPKN-Pad2)") (class "Default")
      (node (ref "U5") (pin "2") (pinfunction "SPKN_2") (pintype "passive"))
    )
    (net (code "82") (name "unconnected-(U5-SPKP-Pad1)") (class "Default")
      (node (ref "U5") (pin "1") (pinfunction "SPKP_1") (pintype "passive"))
    )
    (net (code "83") (name "unconnected-(U5-TX_CTRL-Pad18)") (class "Default")
      (node (ref "U5") (pin "18") (pinfunction "TX_CTRL_18") (pintype "passive"))
    )
    (net (code "84") (name "unconnected-(VD2-Pad2)") (class "Default")
      (node (ref "VD2") (pin "2") (pintype "passive"))
    )
    (net (code "85") (name "unconnected-(VD4-Pad2)") (class "Default")
      (node (ref "VD4") (pin "2") (pintype "passive"))
    )
    (net (code "86") (name "unconnected-(X2-0-Pad7)") (class "Default")
      (node (ref "X2") (pin "7") (pinfunction "0_7") (pintype "passive"))
    )
    (net (code "87") (name "unconnected-(X2-1-Pad8)") (class "Default")
      (node (ref "X2") (pin "8") (pinfunction "1_8") (pintype "passive"))
    )
    (net (code "88") (name "unconnected-(X2-Vpp-Pad5)") (class "Default")
      (node (ref "X2") (pin "5") (pinfunction "Vpp_5") (pintype "passive"))
    )
  )
)
